# ESP32.net
KiCad netlist of a schematic drawn in Altium Designer
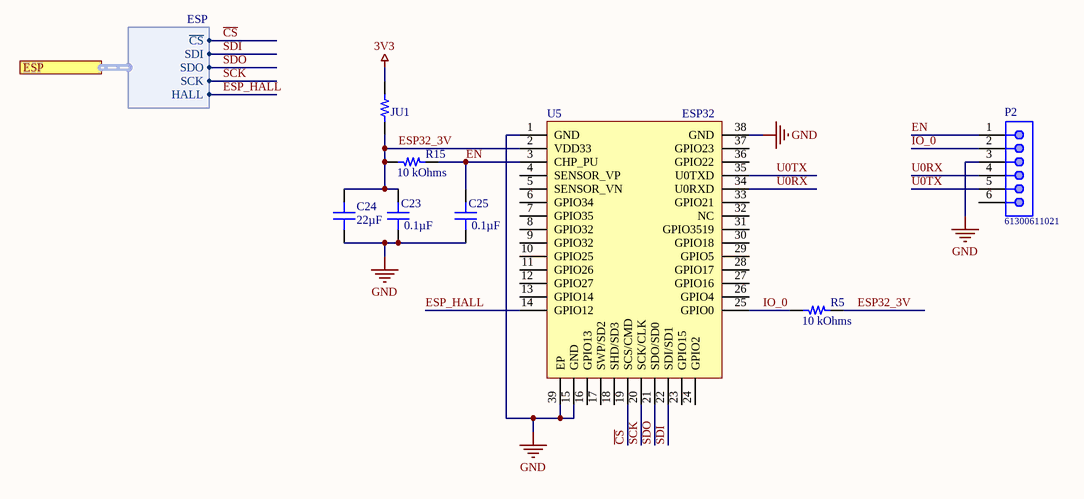
[diagram p0: ESP32.SchDoc]

(export (version "E")
  (design (tool "Eeschema 10.0.6"))
  (components
    (comp (ref "C23")
      (value "0.1µF")
      (footprint "CAP 0603_1608")
      (description "CAP CER 0.1UF 100V 0603 EPOXY")
      (fields
        (field (name "PART NUMBER") "GCG188R92A104KA03D")
        (field (name "MANUFACTURER") "Murata Electronics")
      )
      (libsource (lib "Celestial Altium Library - altium_library") (part "Capacitor"))
    )
    (comp (ref "C24")
      (value "22µF")
      (footprint "CAP 0805_2012")
      (description "CAP CER 22UF 16V X5R 0805")
      (fields
        (field (name "PART NUMBER") "CL21A226MOQNNNE")
        (field (name "MANUFACTURER") "Samsung Electro-Mechanics")
      )
      (libsource (lib "Celestial Altium Library - altium_library") (part "Capacitor"))
    )
    (comp (ref "C25")
      (value "0.1µF")
      (footprint "CAP 0603_1608")
      (description "CAP CER 0.1UF 100V 0603 EPOXY")
      (fields
        (field (name "PART NUMBER") "GCG188R92A104KA03D")
        (field (name "MANUFACTURER") "Murata Electronics")
      )
      (libsource (lib "Celestial Altium Library - altium_library") (part "Capacitor"))
    )
    (comp (ref "JU1")
      (value "~")
      (footprint "RES 0805_2012")
      (description "Jumper")
      (fields
        (field (name "PART NUMBER") "TLRZ2ATTD")
        (field (name "MANUFACTURER") "KOA Speer Electronics, Inc.")
      )
      (libsource (lib "Celestial Altium Library - altium_library") (part "Resistor"))
    )
    (comp (ref "P2")
      (value "61300611021")
      (footprint "61300611021")
      (description "WR-PHD Pin Header, THT, pitch 2.54mm, Single Row, Angled, 6p")
      (fields (field (name "MANUFACTURER") "Wurth Elektronik"))
      (libsource (lib "IC") (part "6pin right angle header - no holes"))
    )
    (comp (ref "R5")
      (value "10 kOhms")
      (footprint "RES 0603_1608")
      (description "RES 10K OHM 0.1% 1/16W 0603")
      (fields
        (field (name "PART NUMBER") "RNCS0603BKE10K0")
        (field (name "MANUFACTURER") "Stackpole Electronics Inc")
      )
      (libsource (lib "Celestial Altium Library - altium_library") (part "Resistor"))
    )
    (comp (ref "R15")
      (value "10 kOhms")
      (footprint "RES 0603_1608")
      (description "RES 10K OHM 0.1% 1/16W 0603")
      (fields
        (field (name "PART NUMBER") "RNCS0603BKE10K0")
        (field (name "MANUFACTURER") "Stackpole Electronics Inc")
      )
      (libsource (lib "Celestial Altium Library - altium_library") (part "Resistor"))
    )
    (comp (ref "U5")
      (value "ESP32")
      (footprint "Espressif ESP32-WROOM-32")
      (libsource (lib "IC") (part "ESP32"))
    )
  )
  (nets
    (net (code "2") (name "/EN") (class "Default")
      (node (ref "C25") (pin "1") (pinfunction "1_1") (pintype "passive"))
      (node (ref "P2") (pin "1") (pinfunction "1_1") (pintype "passive"))
      (node (ref "R15") (pin "1") (pinfunction "1_1") (pintype "passive"))
      (node (ref "U5") (pin "3") (pinfunction "CHP_PU_3") (pintype "passive"))
    )
    (net (code "3") (name "/ESP32_3V") (class "Default")
      (node (ref "C23") (pin "1") (pinfunction "1_1") (pintype "passive"))
      (node (ref "C24") (pin "2") (pinfunction "2_2") (pintype "passive"))
      (node (ref "JU1") (pin "1") (pinfunction "1_1") (pintype "passive"))
      (node (ref "R15") (pin "2") (pinfunction "2_2") (pintype "passive"))
      (node (ref "R5") (pin "1") (pinfunction "1_1") (pintype "passive"))
      (node (ref "U5") (pin "2") (pinfunction "VDD33_2") (pintype "passive"))
    )
    (net (code "4") (name "/ESP_HALL") (class "Default")
      (node (ref "U5") (pin "14") (pinfunction "GPIO12_14") (pintype "passive"))
    )
    (net (code "5") (name "/IO_0") (class "Default")
      (node (ref "P2") (pin "2") (pinfunction "2_2") (pintype "passive"))
      (node (ref "R5") (pin "2") (pinfunction "2_2") (pintype "passive"))
      (node (ref "U5") (pin "25") (pinfunction "GPIO0_25") (pintype "passive"))
    )
    (net (code "6") (name "/SCK") (class "Default")
      (node (ref "U5") (pin "20") (pinfunction "SCK/CLK_20") (pintype "passive"))
    )
    (net (code "7") (name "/SDI") (class "Default")
      (node (ref "U5") (pin "22") (pinfunction "SDI/SD1_22") (pintype "passive"))
    )
    (net (code "8") (name "/SDO") (class "Default")
      (node (ref "U5") (pin "21") (pinfunction "SDO/SD0_21") (pintype "passive"))
    )
    (net (code "9") (name "/U0RX") (class "Default")
      (node (ref "P2") (pin "4") (pinfunction "4_4") (pintype "passive"))
      (node (ref "U5") (pin "34") (pinfunction "U0RXD_34") (pintype "passive"))
    )
    (net (code "10") (name "/U0TX") (class "Default")
      (node (ref "P2") (pin "5") (pinfunction "5_5") (pintype "passive"))
      (node (ref "U5") (pin "35") (pinfunction "U0TXD_35") (pintype "passive"))
    )
    (net (code "12") (name "/~{CS}") (class "Default")
      (node (ref "U5") (pin "19") (pinfunction "SCS/CMD_19") (pintype "passive"))
    )
    (net (code "13") (name "3V3") (class "Default")
      (node (ref "JU1") (pin "2") (pinfunction "2_2") (pintype "passive"))
    )
    (net (code "14") (name "GND") (class "Default")
      (node (ref "C23") (pin "2") (pinfunction "2_2") (pintype "passive"))
      (node (ref "C24") (pin "1") (pinfunction "1_1") (pintype "passive"))
      (node (ref "C25") (pin "2") (pinfunction "2_2") (pintype "passive"))
      (node (ref "P2") (pin "3") (pinfunction "3_3") (pintype "passive"))
      (node (ref "U5") (pin "1") (pinfunction "GND_1") (pintype "passive"))
      (node (ref "U5") (pin "15") (pinfunction "GND_15") (pintype "passive"))
      (node (ref "U5") (pin "38") (pinfunction "GND_38") (pintype "passive"))
      (node (ref "U5") (pin "39") (pinfunction "EP_39") (pintype "passive"))
    )
    (net (code "15") (name "unconnected-(P2-Pad6)") (class "Default")
      (node (ref "P2") (pin "6") (pinfunction "6_6") (pintype "passive"))
    )
    (net (code "16") (name "unconnected-(U5-GPIO2-Pad24)") (class "Default")
      (node (ref "U5") (pin "24") (pinfunction "GPIO2_24") (pintype "passive"))
    )
    (net (code "17") (name "unconnected-(U5-GPIO4-Pad26)") (class "Default")
      (node (ref "U5") (pin "26") (pinfunction "GPIO4_26") (pintype "passive"))
    )
    (net (code "18") (name "unconnected-(U5-GPIO5-Pad29)") (class "Default")
      (node (ref "U5") (pin "29") (pinfunction "GPIO5_29") (pintype "passive"))
    )
    (net (code "19") (name "unconnected-(U5-GPIO13-Pad16)") (class "Default")
      (node (ref "U5") (pin "16") (pinfunction "GPIO13_16") (pintype "passive"))
    )
    (net (code "20") (name "unconnected-(U5-GPIO14-Pad13)") (class "Default")
      (node (ref "U5") (pin "13") (pinfunction "GPIO14_13") (pintype "passive"))
    )
    (net (code "21") (name "unconnected-(U5-GPIO15-Pad23)") (class "Default")
      (node (ref "U5") (pin "23") (pinfunction "GPIO15_23") (pintype "passive"))
    )
    (net (code "22") (name "unconnected-(U5-GPIO16-Pad27)") (class "Default")
      (node (ref "U5") (pin "27") (pinfunction "GPIO16_27") (pintype "passive"))
    )
    (net (code "23") (name "unconnected-(U5-GPIO17-Pad28)") (class "Default")
      (node (ref "U5") (pin "28") (pinfunction "GPIO17_28") (pintype "passive"))
    )
    (net (code "24") (name "unconnected-(U5-GPIO18-Pad30)") (class "Default")
      (node (ref "U5") (pin "30") (pinfunction "GPIO18_30") (pintype "passive"))
    )
    (net (code "25") (name "unconnected-(U5-GPIO21-Pad33)") (class "Default")
      (node (ref "U5") (pin "33") (pinfunction "GPIO21_33") (pintype "passive"))
    )
    (net (code "26") (name "unconnected-(U5-GPIO22-Pad36)") (class "Default")
      (node (ref "U5") (pin "36") (pinfunction "GPIO22_36") (pintype "passive"))
    )
    (net (code "27") (name "unconnected-(U5-GPIO23-Pad37)") (class "Default")
      (node (ref "U5") (pin "37") (pinfunction "GPIO23_37") (pintype "passive"))
    )
    (net (code "28") (name "unconnected-(U5-GPIO25-Pad10)") (class "Default")
      (node (ref "U5") (pin "10") (pinfunction "GPIO25_10") (pintype "passive"))
    )
    (net (code "29") (name "unconnected-(U5-GPIO26-Pad11)") (class "Default")
      (node (ref "U5") (pin "11") (pinfunction "GPIO26_11") (pintype "passive"))
    )
    (net (code "30") (name "unconnected-(U5-GPIO27-Pad12)") (class "Default")
      (node (ref "U5") (pin "12") (pinfunction "GPIO27_12") (pintype "passive"))
    )
    (net (code "31") (name "unconnected-(U5-GPIO32-Pad8)") (class "Default")
      (node (ref "U5") (pin "8") (pinfunction "GPIO32_8") (pintype "passive"))
    )
    (net (code "32") (name "unconnected-(U5-GPIO32-Pad9)") (class "Default")
      (node (ref "U5") (pin "9") (pinfunction "GPIO32_9") (pintype "passive"))
    )
    (net (code "33") (name "unconnected-(U5-GPIO34-Pad6)") (class "Default")
      (node (ref "U5") (pin "6") (pinfunction "GPIO34_6") (pintype "passive"))
    )
    (net (code "34") (name "unconnected-(U5-GPIO35-Pad7)") (class "Default")
      (node (ref "U5") (pin "7") (pinfunction "GPIO35_7") (pintype "passive"))
    )
    (net (code "35") (name "unconnected-(U5-GPIO3519-Pad31)") (class "Default")
      (node (ref "U5") (pin "31") (pinfunction "GPIO3519_31") (pintype "passive"))
    )
    (net (code "36") (name "unconnected-(U5-NC-Pad32)") (class "Default")
      (node (ref "U5") (pin "32") (pinfunction "NC_32") (pintype "passive"))
    )
    (net (code "37") (name "unconnected-(U5-SENSOR_VN-Pad5)") (class "Default")
      (node (ref "U5") (pin "5") (pinfunction "SENSOR_VN_5") (pintype "passive"))
    )
    (net (code "38") (name "unconnected-(U5-SENSOR_VP-Pad4)") (class "Default")
      (node (ref "U5") (pin "4") (pinfunction "SENSOR_VP_4") (pintype "passive"))
    )
    (net (code "39") (name "unconnected-(U5-SHD{slash}SD3-Pad18)") (class "Default")
      (node (ref "U5") (pin "18") (pinfunction "SHD/SD3_18") (pintype "passive"))
    )
    (net (code "40") (name "unconnected-(U5-SWP{slash}SD2-Pad17)") (class "Default")
      (node (ref "U5") (pin "17") (pinfunction "SWP/SD2_17") (pintype "passive"))
    )
  )
)
